# master_jorge3newIMU.net
KiCad netlist of a schematic drawn in EAGLE
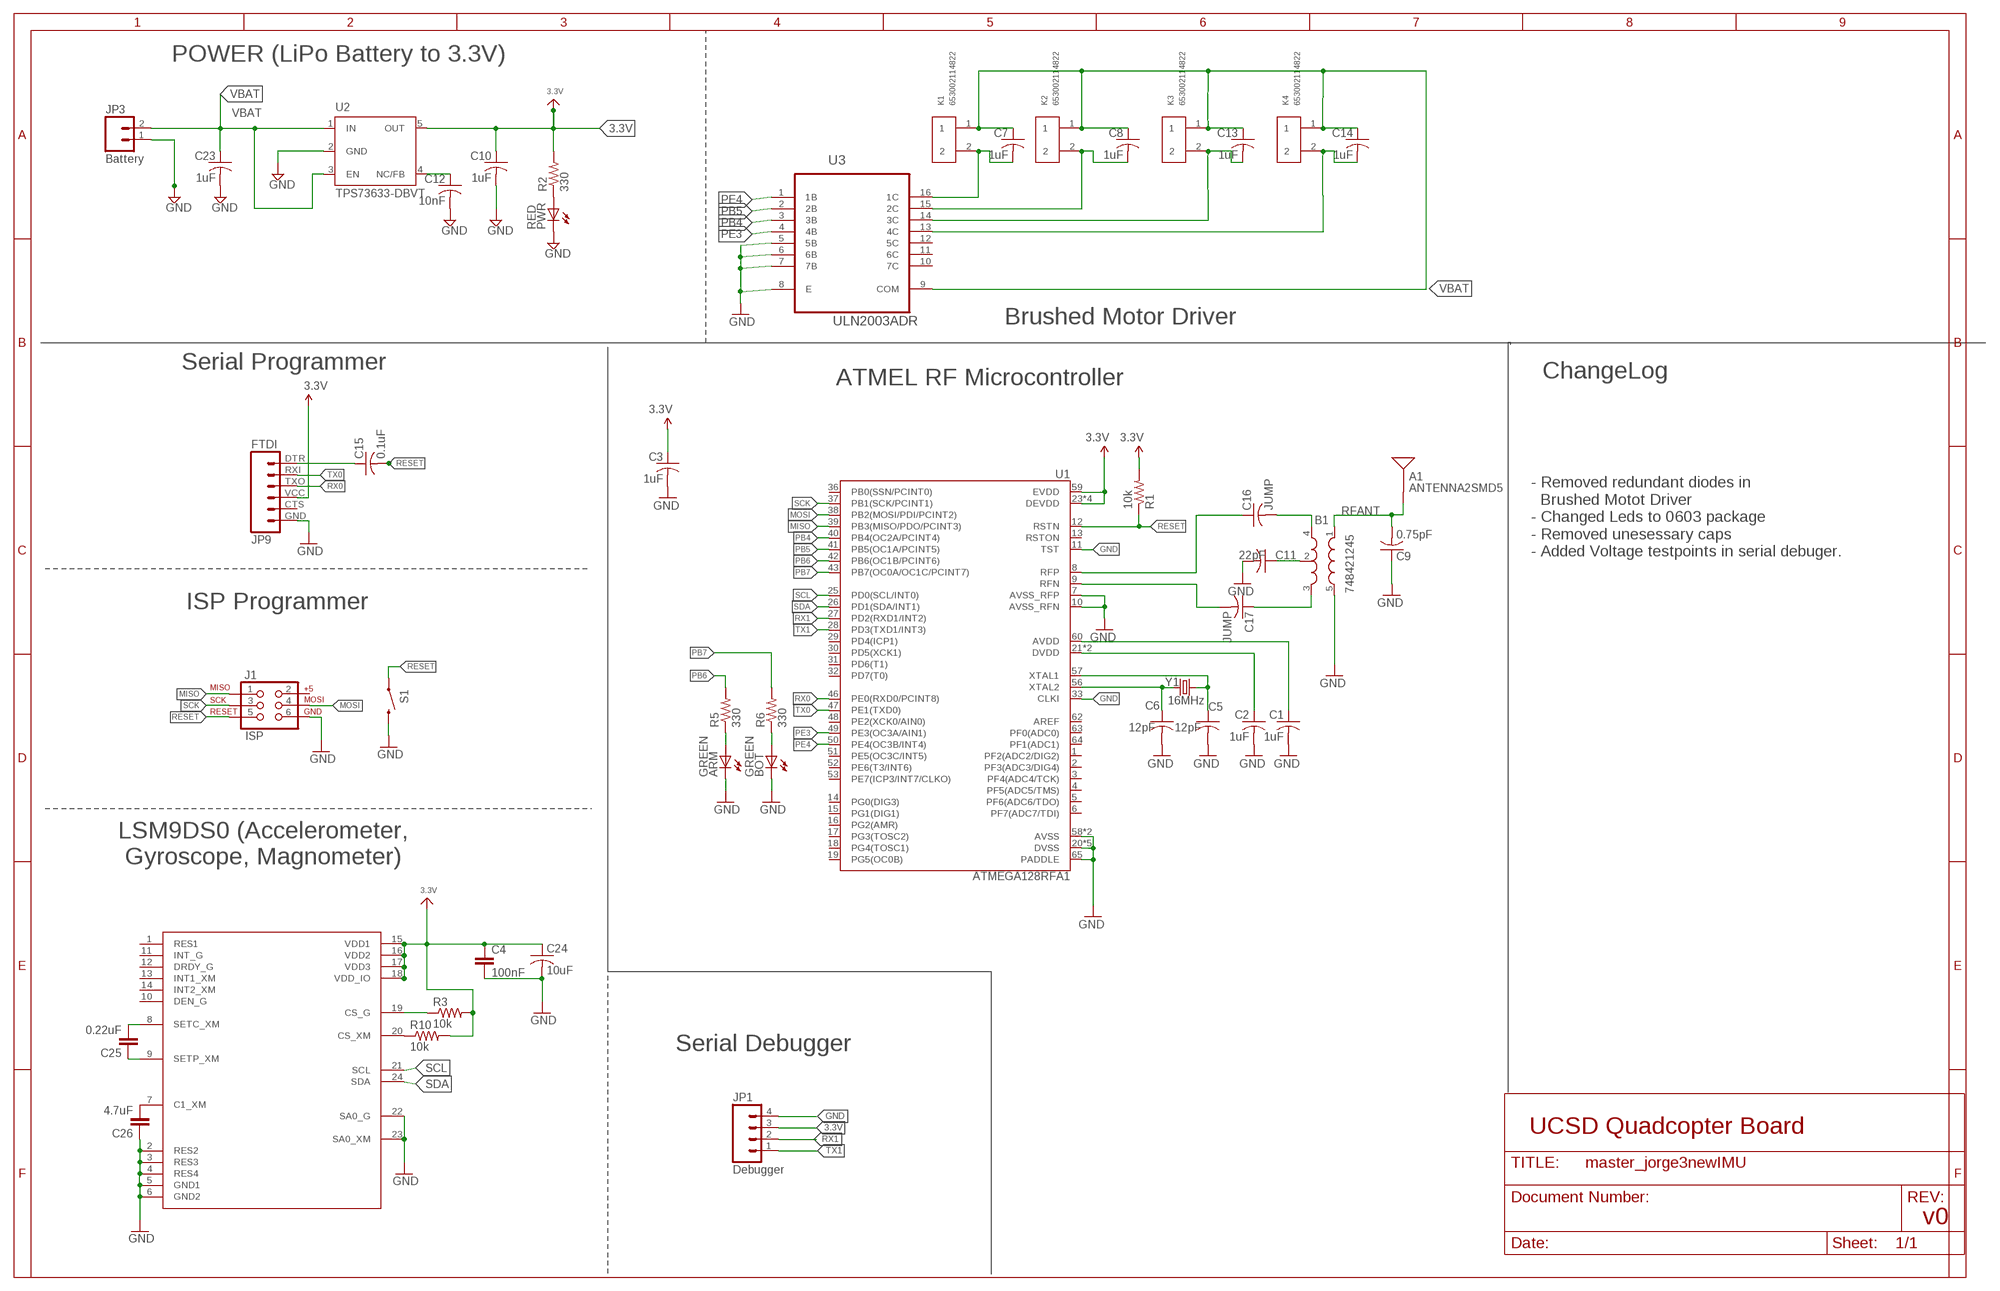
[diagram p0: schematic, sheet 1]

(export (version "E")
  (design (tool "Eeschema 10.0.6"))
  (components
    (comp (ref "A1")
      (value "ANTENNA2SMD5")
      (footprint "eagle-import:ANTENNA-CHIP5")
      (libsource (lib "eagle-import") (part "ANTENNA2SMD5"))
    )
    (comp (ref "ARM")
      (value "GREEN")
      (footprint "eagle-import:CHIP-LED0805")
      (libsource (lib "eagle-import") (part "LEDCHIP-LED0805"))
    )
    (comp (ref "B1")
      (value "748421245")
      (footprint "eagle-import:BALUN")
      (libsource (lib "eagle-import") (part "BALUN0805"))
    )
    (comp (ref "BOT")
      (value "GREEN")
      (footprint "eagle-import:CHIP-LED0805")
      (libsource (lib "eagle-import") (part "LEDCHIP-LED0805"))
    )
    (comp (ref "C1")
      (value "1uF")
      (footprint "eagle-import:C0805")
      (libsource (lib "eagle-import") (part "resistor_C-USC0805"))
    )
    (comp (ref "C2")
      (value "1uF")
      (footprint "eagle-import:C0805")
      (libsource (lib "eagle-import") (part "resistor_C-USC0805"))
    )
    (comp (ref "C3")
      (value "1uF")
      (footprint "eagle-import:C0805")
      (libsource (lib "eagle-import") (part "resistor_C-USC0805"))
    )
    (comp (ref "C4")
      (value "100nF")
      (footprint "eagle-import:0805")
      (libsource (lib "eagle-import") (part "CAP0805"))
    )
    (comp (ref "C5")
      (value "12pF")
      (footprint "eagle-import:C0805")
      (libsource (lib "eagle-import") (part "resistor_C-USC0805"))
    )
    (comp (ref "C6")
      (value "12pF")
      (footprint "eagle-import:C0805")
      (libsource (lib "eagle-import") (part "resistor_C-USC0805"))
    )
    (comp (ref "C7")
      (value "1uF")
      (footprint "eagle-import:C0805")
      (libsource (lib "eagle-import") (part "resistor_C-USC0805"))
    )
    (comp (ref "C8")
      (value "1uF")
      (footprint "eagle-import:C0805")
      (libsource (lib "eagle-import") (part "resistor_C-USC0805"))
    )
    (comp (ref "C9")
      (value "0.75pF")
      (footprint "eagle-import:C0805")
      (libsource (lib "eagle-import") (part "resistor_C-USC0805"))
    )
    (comp (ref "C10")
      (value "1uF")
      (footprint "eagle-import:C0805")
      (libsource (lib "eagle-import") (part "resistor_C-USC0805"))
    )
    (comp (ref "C11")
      (value "22pF")
      (footprint "eagle-import:C0805")
      (libsource (lib "eagle-import") (part "resistor_C-USC0805"))
    )
    (comp (ref "C12")
      (value "10nF")
      (footprint "eagle-import:C0805")
      (libsource (lib "eagle-import") (part "resistor_C-USC0805"))
    )
    (comp (ref "C13")
      (value "1uF")
      (footprint "eagle-import:C0805")
      (libsource (lib "eagle-import") (part "resistor_C-USC0805"))
    )
    (comp (ref "C14")
      (value "1uF")
      (footprint "eagle-import:C0805")
      (libsource (lib "eagle-import") (part "resistor_C-USC0805"))
    )
    (comp (ref "C15")
      (value "0.1uF")
      (footprint "eagle-import:C0805")
      (libsource (lib "eagle-import") (part "resistor_C-USC0805"))
    )
    (comp (ref "C16")
      (value "JUMP")
      (footprint "eagle-import:C0805")
      (libsource (lib "eagle-import") (part "resistor_C-USC0805"))
    )
    (comp (ref "C17")
      (value "JUMP")
      (footprint "eagle-import:C0805")
      (libsource (lib "eagle-import") (part "resistor_C-USC0805"))
    )
    (comp (ref "C23")
      (value "1uF")
      (footprint "eagle-import:C0805")
      (libsource (lib "eagle-import") (part "resistor_C-USC0805"))
    )
    (comp (ref "C24")
      (value "10uF")
      (footprint "eagle-import:C0805")
      (libsource (lib "eagle-import") (part "C-USC0805"))
    )
    (comp (ref "C25")
      (value "0.22uF")
      (footprint "eagle-import:0805")
      (libsource (lib "eagle-import") (part "CAP0805"))
    )
    (comp (ref "C26")
      (value "4.7uF")
      (footprint "eagle-import:0805")
      (libsource (lib "eagle-import") (part "CAP0805"))
    )
    (comp (ref "J1")
      (value "ISP")
      (footprint "eagle-import:2X3-NS")
      (libsource (lib "eagle-import") (part "AVR_SPI_PRG_6NS"))
    )
    (comp (ref "JP1")
      (value "Debugger")
      (footprint "eagle-import:1X04")
      (libsource (lib "eagle-import") (part "M04PTH"))
    )
    (comp (ref "JP3")
      (value "Battery")
      (footprint "eagle-import:1X02")
      (libsource (lib "eagle-import") (part "M02PTH"))
    )
    (comp (ref "JP9")
      (value "FTDI")
      (footprint "eagle-import:FTDI_BASIC")
      (libsource (lib "eagle-import") (part "FTDI_BASICPTH"))
    )
    (comp (ref "K1")
      (value "653002114822")
      (footprint "eagle-import:653002114822")
      (libsource (lib "eagle-import") (part "653002114822"))
    )
    (comp (ref "K2")
      (value "653002114822")
      (footprint "eagle-import:653002114822")
      (libsource (lib "eagle-import") (part "653002114822"))
    )
    (comp (ref "K3")
      (value "653002114822")
      (footprint "eagle-import:653002114822")
      (libsource (lib "eagle-import") (part "653002114822"))
    )
    (comp (ref "K4")
      (value "653002114822")
      (footprint "eagle-import:653002114822")
      (libsource (lib "eagle-import") (part "653002114822"))
    )
    (comp (ref "PWR")
      (value "RED")
      (footprint "eagle-import:CHIP-LED0805")
      (libsource (lib "eagle-import") (part "LEDCHIP-LED0805"))
    )
    (comp (ref "R1")
      (value "10k")
      (footprint "eagle-import:R0805")
      (libsource (lib "eagle-import") (part "R-US_R0805"))
    )
    (comp (ref "R2")
      (value "330")
      (footprint "eagle-import:R0805")
      (libsource (lib "eagle-import") (part "R-US_R0805"))
    )
    (comp (ref "R3")
      (value "10k")
      (footprint "eagle-import:0805")
      (libsource (lib "eagle-import") (part "RESISTOR0805-RES"))
    )
    (comp (ref "R5")
      (value "330")
      (footprint "eagle-import:R0805")
      (libsource (lib "eagle-import") (part "R-US_R0805"))
    )
    (comp (ref "R6")
      (value "330")
      (footprint "eagle-import:R0805")
      (libsource (lib "eagle-import") (part "R-US_R0805"))
    )
    (comp (ref "R10")
      (value "10k")
      (footprint "eagle-import:0805")
      (libsource (lib "eagle-import") (part "RESISTOR0805-RES"))
    )
    (comp (ref "S1")
      (value "SWITCH-MOMENTARY-2SMD")
      (footprint "eagle-import:TACTILE_SWITCH_SMD")
      (libsource (lib "eagle-import") (part "SWITCH-MOMENTARY-2SMD"))
    )
    (comp (ref "U1")
      (value "ATMEGA128RFA1")
      (footprint "eagle-import:QFN-64")
      (libsource (lib "eagle-import") (part "ATMEGA128RFA1"))
    )
    (comp (ref "U2")
      (value "TPS73633-DBVT")
      (footprint "eagle-import:SOT23-DBV")
      (libsource (lib "eagle-import") (part "TPS73633-DBVT"))
    )
    (comp (ref "U3")
      (value "ULN2003ADR")
      (footprint "eagle-import:SOIC127P600X175-16N")
      (libsource (lib "eagle-import") (part "ULN2003ADR"))
    )
    (comp (ref "U4")
      (value "LSM9DS0")
      (footprint "eagle-import:LGA-24")
      (libsource (lib "eagle-import") (part "LSM9DS0"))
    )
    (comp (ref "Y1")
      (value "16MHz")
      (footprint "eagle-import:CRYSTAL-SMD-5X3")
      (libsource (lib "eagle-import") (part "CRYSTAL5X3"))
    )
  )
  (nets
    (net (code "1") (name "/RFANT") (class "Default")
      (node (ref "A1") (pin "FEED") (pinfunction "SIGNAL_FEED") (pintype "bidirectional"))
      (node (ref "B1") (pin "1") (pinfunction "IN_1") (pintype "bidirectional"))
      (node (ref "C9") (pin "2") (pinfunction "2_2") (pintype "passive"))
    )
    (net (code "2") (name "3.3V") (class "Default")
      (node (ref "C10") (pin "1") (pinfunction "1_1") (pintype "passive"))
      (node (ref "C24") (pin "1") (pinfunction "1_1") (pintype "passive"))
      (node (ref "C3") (pin "1") (pinfunction "1_1") (pintype "passive"))
      (node (ref "C4") (pin "1") (pinfunction "1_1") (pintype "passive"))
      (node (ref "JP1") (pin "3") (pinfunction "3_3") (pintype "passive"))
      (node (ref "JP9") (pin "VCC") (pinfunction "4_VCC") (pintype "passive"))
      (node (ref "R1") (pin "2") (pinfunction "2_2") (pintype "passive"))
      (node (ref "R10") (pin "2") (pinfunction "2_2") (pintype "passive"))
      (node (ref "R2") (pin "2") (pinfunction "2_2") (pintype "passive"))
      (node (ref "R3") (pin "2") (pinfunction "2_2") (pintype "passive"))
      (node (ref "U1") (pin "23") (pinfunction "DEVDD_23") (pintype "bidirectional"))
      (node (ref "U1") (pin "34") (pinfunction "DEVDD_34") (pintype "bidirectional"))
      (node (ref "U1") (pin "44") (pinfunction "DEVDD_44") (pintype "bidirectional"))
      (node (ref "U1") (pin "54") (pinfunction "DEVDD_54") (pintype "bidirectional"))
      (node (ref "U1") (pin "59") (pinfunction "EVDD_59") (pintype "bidirectional"))
      (node (ref "U2") (pin "5") (pinfunction "OUT_5") (pintype "passive"))
      (node (ref "U4") (pin "15") (pinfunction "VDD1_15") (pintype "bidirectional"))
      (node (ref "U4") (pin "16") (pinfunction "VDD2_16") (pintype "bidirectional"))
      (node (ref "U4") (pin "17") (pinfunction "VDD3_17") (pintype "bidirectional"))
      (node (ref "U4") (pin "18") (pinfunction "VDD_IO_18") (pintype "bidirectional"))
    )
    (net (code "3") (name "GND") (class "Default")
      (node (ref "ARM") (pin "C") (pinfunction "C_C") (pintype "passive"))
      (node (ref "B1") (pin "5") (pinfunction "GND_5") (pintype "bidirectional"))
      (node (ref "BOT") (pin "C") (pinfunction "C_C") (pintype "passive"))
      (node (ref "C1") (pin "2") (pinfunction "2_2") (pintype "passive"))
      (node (ref "C10") (pin "2") (pinfunction "2_2") (pintype "passive"))
      (node (ref "C11") (pin "2") (pinfunction "2_2") (pintype "passive"))
      (node (ref "C12") (pin "2") (pinfunction "2_2") (pintype "passive"))
      (node (ref "C2") (pin "2") (pinfunction "2_2") (pintype "passive"))
      (node (ref "C23") (pin "2") (pinfunction "2_2") (pintype "passive"))
      (node (ref "C24") (pin "2") (pinfunction "2_2") (pintype "passive"))
      (node (ref "C26") (pin "1") (pinfunction "1_1") (pintype "passive"))
      (node (ref "C3") (pin "2") (pinfunction "2_2") (pintype "passive"))
      (node (ref "C4") (pin "2") (pinfunction "2_2") (pintype "passive"))
      (node (ref "C5") (pin "2") (pinfunction "2_2") (pintype "passive"))
      (node (ref "C6") (pin "2") (pinfunction "2_2") (pintype "passive"))
      (node (ref "C9") (pin "1") (pinfunction "1_1") (pintype "passive"))
      (node (ref "J1") (pin "6") (pinfunction "6_6") (pintype "passive"))
      (node (ref "JP1") (pin "4") (pinfunction "4_4") (pintype "passive"))
      (node (ref "JP3") (pin "1") (pinfunction "1_1") (pintype "passive"))
      (node (ref "JP9") (pin "GND") (pinfunction "6_GND") (pintype "passive"))
      (node (ref "PWR") (pin "C") (pinfunction "C_C") (pintype "passive"))
      (node (ref "S1") (pin "3") (pinfunction "2_3") (pintype "passive"))
      (node (ref "U1") (pin "10") (pinfunction "AVSS_RFN_10") (pintype "bidirectional"))
      (node (ref "U1") (pin "11") (pinfunction "TST_11") (pintype "bidirectional"))
      (node (ref "U1") (pin "20") (pinfunction "DVSS_20") (pintype "bidirectional"))
      (node (ref "U1") (pin "24") (pinfunction "DVSS_24") (pintype "bidirectional"))
      (node (ref "U1") (pin "33") (pinfunction "CLKI_33") (pintype "bidirectional"))
      (node (ref "U1") (pin "35") (pinfunction "DVSS_35") (pintype "bidirectional"))
      (node (ref "U1") (pin "45") (pinfunction "DVSS_45") (pintype "bidirectional"))
      (node (ref "U1") (pin "55") (pinfunction "DVSS_55") (pintype "bidirectional"))
      (node (ref "U1") (pin "58") (pinfunction "AVSS_58") (pintype "bidirectional"))
      (node (ref "U1") (pin "61") (pinfunction "AVSS_61") (pintype "bidirectional"))
      (node (ref "U1") (pin "65") (pinfunction "PADDLE_65") (pintype "bidirectional"))
      (node (ref "U1") (pin "7") (pinfunction "AVSS_RFP_7") (pintype "bidirectional"))
      (node (ref "U2") (pin "2") (pinfunction "GND_2") (pintype "input"))
      (node (ref "U3") (pin "5") (pinfunction "5B_5") (pintype "input"))
      (node (ref "U3") (pin "6") (pinfunction "6B_6") (pintype "input"))
      (node (ref "U3") (pin "7") (pinfunction "7B_7") (pintype "input"))
      (node (ref "U3") (pin "8") (pinfunction "E_8") (pintype "input"))
      (node (ref "U4") (pin "2") (pinfunction "RES2_2") (pintype "bidirectional"))
      (node (ref "U4") (pin "22") (pinfunction "SA0_G_22") (pintype "bidirectional"))
      (node (ref "U4") (pin "23") (pinfunction "SA0_XM_23") (pintype "bidirectional"))
      (node (ref "U4") (pin "3") (pinfunction "RES3_3") (pintype "bidirectional"))
      (node (ref "U4") (pin "4") (pinfunction "RES4_4") (pintype "bidirectional"))
      (node (ref "U4") (pin "5") (pinfunction "GND1_5") (pintype "bidirectional"))
      (node (ref "U4") (pin "6") (pinfunction "GND2_6") (pintype "bidirectional"))
    )
    (net (code "4") (name "MISO") (class "Default")
      (node (ref "J1") (pin "1") (pinfunction "1_1") (pintype "passive"))
      (node (ref "U1") (pin "39") (pinfunction "PB3(MISO/PDO/PCINT3)_39") (pintype "bidirectional"))
    )
    (net (code "5") (name "MOSI") (class "Default")
      (node (ref "J1") (pin "4") (pinfunction "4_4") (pintype "passive"))
      (node (ref "U1") (pin "38") (pinfunction "PB2(MOSI/PDI/PCINT2)_38") (pintype "bidirectional"))
    )
    (net (code "6") (name "Net-(ARM-PadA)") (class "Default")
      (node (ref "ARM") (pin "A") (pinfunction "A_A") (pintype "passive"))
      (node (ref "R5") (pin "1") (pinfunction "1_1") (pintype "passive"))
    )
    (net (code "7") (name "Net-(B1-GND-Pad2)") (class "Default")
      (node (ref "B1") (pin "2") (pinfunction "GND_2") (pintype "bidirectional"))
      (node (ref "C11") (pin "1") (pinfunction "1_1") (pintype "passive"))
    )
    (net (code "8") (name "Net-(B1-OUT1)") (class "Default")
      (node (ref "B1") (pin "4") (pinfunction "OUT1_4") (pintype "bidirectional"))
      (node (ref "C16") (pin "2") (pinfunction "2_2") (pintype "passive"))
    )
    (net (code "9") (name "Net-(B1-OUT2)") (class "Default")
      (node (ref "B1") (pin "3") (pinfunction "OUT2_3") (pintype "bidirectional"))
      (node (ref "C17") (pin "1") (pinfunction "1_1") (pintype "passive"))
    )
    (net (code "10") (name "Net-(BOT-PadA)") (class "Default")
      (node (ref "BOT") (pin "A") (pinfunction "A_A") (pintype "passive"))
      (node (ref "R6") (pin "1") (pinfunction "1_1") (pintype "passive"))
    )
    (net (code "11") (name "Net-(C2-Pad1)") (class "Default")
      (node (ref "C2") (pin "1") (pinfunction "1_1") (pintype "passive"))
      (node (ref "U1") (pin "21") (pinfunction "DVDD_21") (pintype "bidirectional"))
      (node (ref "U1") (pin "22") (pinfunction "DVDD_22") (pintype "bidirectional"))
    )
    (net (code "12") (name "Net-(JP9-1)") (class "Default")
      (node (ref "C15") (pin "1") (pinfunction "1_1") (pintype "passive"))
      (node (ref "JP9") (pin "DTR") (pinfunction "1_DTR") (pintype "passive"))
    )
    (net (code "13") (name "Net-(PWR-PadA)") (class "Default")
      (node (ref "PWR") (pin "A") (pinfunction "A_A") (pintype "passive"))
      (node (ref "R2") (pin "1") (pinfunction "1_1") (pintype "passive"))
    )
    (net (code "14") (name "Net-(U1-AVDD)") (class "Default")
      (node (ref "C1") (pin "1") (pinfunction "1_1") (pintype "passive"))
      (node (ref "U1") (pin "60") (pinfunction "AVDD_60") (pintype "bidirectional"))
    )
    (net (code "15") (name "Net-(U1-RFN)") (class "Default")
      (node (ref "C17") (pin "2") (pinfunction "2_2") (pintype "passive"))
      (node (ref "U1") (pin "9") (pinfunction "RFN_9") (pintype "bidirectional"))
    )
    (net (code "16") (name "Net-(U1-RFP)") (class "Default")
      (node (ref "C16") (pin "1") (pinfunction "1_1") (pintype "passive"))
      (node (ref "U1") (pin "8") (pinfunction "RFP_8") (pintype "bidirectional"))
    )
    (net (code "17") (name "Net-(U1-XTAL1)") (class "Default")
      (node (ref "C5") (pin "1") (pinfunction "1_1") (pintype "passive"))
      (node (ref "U1") (pin "57") (pinfunction "XTAL1_57") (pintype "bidirectional"))
      (node (ref "Y1") (pin "3") (pinfunction "2_3") (pintype "passive"))
    )
    (net (code "18") (name "Net-(U1-XTAL2)") (class "Default")
      (node (ref "C6") (pin "1") (pinfunction "1_1") (pintype "passive"))
      (node (ref "U1") (pin "56") (pinfunction "XTAL2_56") (pintype "bidirectional"))
      (node (ref "Y1") (pin "1") (pinfunction "1_1") (pintype "passive"))
    )
    (net (code "19") (name "Net-(U2-NC{slash}FB)") (class "Default")
      (node (ref "C12") (pin "1") (pinfunction "1_1") (pintype "passive"))
      (node (ref "U2") (pin "4") (pinfunction "NC/FB_4") (pintype "passive"))
    )
    (net (code "20") (name "Net-(U3-1C)") (class "Default")
      (node (ref "C7") (pin "2") (pinfunction "2_2") (pintype "passive"))
      (node (ref "K1") (pin "2") (pinfunction "2_2") (pintype "bidirectional"))
      (node (ref "U3") (pin "16") (pinfunction "1C_16") (pintype "output"))
    )
    (net (code "21") (name "Net-(U3-2C)") (class "Default")
      (node (ref "C8") (pin "2") (pinfunction "2_2") (pintype "passive"))
      (node (ref "K2") (pin "2") (pinfunction "2_2") (pintype "bidirectional"))
      (node (ref "U3") (pin "15") (pinfunction "2C_15") (pintype "output"))
    )
    (net (code "22") (name "Net-(U3-3C)") (class "Default")
      (node (ref "C13") (pin "2") (pinfunction "2_2") (pintype "passive"))
      (node (ref "K3") (pin "2") (pinfunction "2_2") (pintype "bidirectional"))
      (node (ref "U3") (pin "14") (pinfunction "3C_14") (pintype "output"))
    )
    (net (code "23") (name "Net-(U3-4C)") (class "Default")
      (node (ref "C14") (pin "2") (pinfunction "2_2") (pintype "passive"))
      (node (ref "K4") (pin "2") (pinfunction "2_2") (pintype "bidirectional"))
      (node (ref "U3") (pin "13") (pinfunction "4C_13") (pintype "output"))
    )
    (net (code "24") (name "Net-(U4-C1_XM)") (class "Default")
      (node (ref "C26") (pin "2") (pinfunction "2_2") (pintype "passive"))
      (node (ref "U4") (pin "7") (pinfunction "C1_XM_7") (pintype "bidirectional"))
    )
    (net (code "25") (name "Net-(U4-CS_G)") (class "Default")
      (node (ref "R3") (pin "1") (pinfunction "1_1") (pintype "passive"))
      (node (ref "U4") (pin "19") (pinfunction "CS_G_19") (pintype "bidirectional"))
    )
    (net (code "26") (name "Net-(U4-CS_XM)") (class "Default")
      (node (ref "R10") (pin "1") (pinfunction "1_1") (pintype "passive"))
      (node (ref "U4") (pin "20") (pinfunction "CS_XM_20") (pintype "bidirectional"))
    )
    (net (code "27") (name "Net-(U4-SETC_XM)") (class "Default")
      (node (ref "C25") (pin "2") (pinfunction "2_2") (pintype "passive"))
      (node (ref "U4") (pin "8") (pinfunction "SETC_XM_8") (pintype "bidirectional"))
    )
    (net (code "28") (name "Net-(U4-SETP_XM)") (class "Default")
      (node (ref "C25") (pin "1") (pinfunction "1_1") (pintype "passive"))
      (node (ref "U4") (pin "9") (pinfunction "SETP_XM_9") (pintype "bidirectional"))
    )
    (net (code "29") (name "PB4") (class "Default")
      (node (ref "U1") (pin "40") (pinfunction "PB4(OC2A/PCINT4)_40") (pintype "bidirectional"))
      (node (ref "U3") (pin "3") (pinfunction "3B_3") (pintype "input"))
    )
    (net (code "30") (name "PB5") (class "Default")
      (node (ref "U1") (pin "41") (pinfunction "PB5(OC1A/PCINT5)_41") (pintype "bidirectional"))
      (node (ref "U3") (pin "2") (pinfunction "2B_2") (pintype "input"))
    )
    (net (code "31") (name "PB6") (class "Default")
      (node (ref "R5") (pin "2") (pinfunction "2_2") (pintype "passive"))
      (node (ref "U1") (pin "42") (pinfunction "PB6(OC1B/PCINT6)_42") (pintype "bidirectional"))
    )
    (net (code "32") (name "PB7") (class "Default")
      (node (ref "R6") (pin "2") (pinfunction "2_2") (pintype "passive"))
      (node (ref "U1") (pin "43") (pinfunction "PB7(OC0A/OC1C/PCINT7)_43") (pintype "bidirectional"))
    )
    (net (code "33") (name "PE3") (class "Default")
      (node (ref "U1") (pin "49") (pinfunction "PE3(OC3A/AIN1)_49") (pintype "bidirectional"))
      (node (ref "U3") (pin "4") (pinfunction "4B_4") (pintype "input"))
    )
    (net (code "34") (name "PE4") (class "Default")
      (node (ref "U1") (pin "50") (pinfunction "PE4(OC3B/INT4)_50") (pintype "bidirectional"))
      (node (ref "U3") (pin "1") (pinfunction "1B_1") (pintype "input"))
    )
    (net (code "35") (name "RESET") (class "Default")
      (node (ref "C15") (pin "2") (pinfunction "2_2") (pintype "passive"))
      (node (ref "J1") (pin "5") (pinfunction "5_5") (pintype "passive"))
      (node (ref "R1") (pin "1") (pinfunction "1_1") (pintype "passive"))
      (node (ref "S1") (pin "1") (pinfunction "1_1") (pintype "passive"))
      (node (ref "U1") (pin "12") (pinfunction "RSTN_12") (pintype "bidirectional"))
    )
    (net (code "36") (name "RX0") (class "Default")
      (node (ref "JP9") (pin "TXO") (pinfunction "3_TXO") (pintype "passive"))
      (node (ref "U1") (pin "46") (pinfunction "PE0(RXD0/PCINT8)_46") (pintype "bidirectional"))
    )
    (net (code "37") (name "RX1") (class "Default")
      (node (ref "JP1") (pin "2") (pinfunction "2_2") (pintype "passive"))
      (node (ref "U1") (pin "27") (pinfunction "PD2(RXD1/INT2)_27") (pintype "bidirectional"))
    )
    (net (code "38") (name "SCK") (class "Default")
      (node (ref "J1") (pin "3") (pinfunction "3_3") (pintype "passive"))
      (node (ref "U1") (pin "37") (pinfunction "PB1(SCK/PCINT1)_37") (pintype "bidirectional"))
    )
    (net (code "39") (name "SCL") (class "Default")
      (node (ref "U1") (pin "25") (pinfunction "PD0(SCL/INT0)_25") (pintype "bidirectional"))
      (node (ref "U4") (pin "21") (pinfunction "SCL_21") (pintype "bidirectional"))
    )
    (net (code "40") (name "SDA") (class "Default")
      (node (ref "U1") (pin "26") (pinfunction "PD1(SDA/INT1)_26") (pintype "bidirectional"))
      (node (ref "U4") (pin "24") (pinfunction "SDA_24") (pintype "bidirectional"))
    )
    (net (code "41") (name "TX0") (class "Default")
      (node (ref "JP9") (pin "RXI") (pinfunction "2_RXI") (pintype "passive"))
      (node (ref "U1") (pin "47") (pinfunction "PE1(TXD0)_47") (pintype "bidirectional"))
    )
    (net (code "42") (name "TX1") (class "Default")
      (node (ref "JP1") (pin "1") (pinfunction "1_1") (pintype "passive"))
      (node (ref "U1") (pin "28") (pinfunction "PD3(TXD1/INT3)_28") (pintype "bidirectional"))
    )
    (net (code "43") (name "VBAT") (class "Default")
      (node (ref "C13") (pin "1") (pinfunction "1_1") (pintype "passive"))
      (node (ref "C14") (pin "1") (pinfunction "1_1") (pintype "passive"))
      (node (ref "C23") (pin "1") (pinfunction "1_1") (pintype "passive"))
      (node (ref "C7") (pin "1") (pinfunction "1_1") (pintype "passive"))
      (node (ref "C8") (pin "1") (pinfunction "1_1") (pintype "passive"))
      (node (ref "JP3") (pin "2") (pinfunction "2_2") (pintype "passive"))
      (node (ref "K1") (pin "1") (pinfunction "1_1") (pintype "bidirectional"))
      (node (ref "K2") (pin "1") (pinfunction "1_1") (pintype "bidirectional"))
      (node (ref "K3") (pin "1") (pinfunction "1_1") (pintype "bidirectional"))
      (node (ref "K4") (pin "1") (pinfunction "1_1") (pintype "bidirectional"))
      (node (ref "U2") (pin "1") (pinfunction "IN_1") (pintype "input"))
      (node (ref "U2") (pin "3") (pinfunction "EN_3") (pintype "power_in"))
      (node (ref "U3") (pin "9") (pinfunction "COM_9") (pintype "output"))
    )
    (net (code "44") (name "unconnected-(J1-Pad2)") (class "Default")
      (node (ref "J1") (pin "2") (pinfunction "2_2") (pintype "passive"))
    )
    (net (code "45") (name "unconnected-(JP9-5-PadCTS)") (class "Default")
      (node (ref "JP9") (pin "CTS") (pinfunction "5_CTS") (pintype "passive"))
    )
    (net (code "46") (name "unconnected-(U1-AREF-Pad62)") (class "Default")
      (node (ref "U1") (pin "62") (pinfunction "AREF_62") (pintype "bidirectional"))
    )
    (net (code "47") (name "unconnected-(U1-PB0(SSN{slash}PCINT0)-Pad36)") (class "Default")
      (node (ref "U1") (pin "36") (pinfunction "PB0(SSN/PCINT0)_36") (pintype "bidirectional"))
    )
    (net (code "48") (name "unconnected-(U1-PD4(ICP1)-Pad29)") (class "Default")
      (node (ref "U1") (pin "29") (pinfunction "PD4(ICP1)_29") (pintype "bidirectional"))
    )
    (net (code "49") (name "unconnected-(U1-PD5(XCK1)-Pad30)") (class "Default")
      (node (ref "U1") (pin "30") (pinfunction "PD5(XCK1)_30") (pintype "bidirectional"))
    )
    (net (code "50") (name "unconnected-(U1-PD6(T1)-Pad31)") (class "Default")
      (node (ref "U1") (pin "31") (pinfunction "PD6(T1)_31") (pintype "bidirectional"))
    )
    (net (code "51") (name "unconnected-(U1-PD7(T0)-Pad32)") (class "Default")
      (node (ref "U1") (pin "32") (pinfunction "PD7(T0)_32") (pintype "bidirectional"))
    )
    (net (code "52") (name "unconnected-(U1-PE2(XCK0{slash}AIN0)-Pad48)") (class "Default")
      (node (ref "U1") (pin "48") (pinfunction "PE2(XCK0/AIN0)_48") (pintype "bidirectional"))
    )
    (net (code "53") (name "unconnected-(U1-PE5(OC3C{slash}INT5)-Pad51)") (class "Default")
      (node (ref "U1") (pin "51") (pinfunction "PE5(OC3C/INT5)_51") (pintype "bidirectional"))
    )
    (net (code "54") (name "unconnected-(U1-PE6(T3{slash}INT6)-Pad52)") (class "Default")
      (node (ref "U1") (pin "52") (pinfunction "PE6(T3/INT6)_52") (pintype "bidirectional"))
    )
    (net (code "55") (name "unconnected-(U1-PE7(ICP3{slash}INT7{slash}CLKO)-Pad53)") (class "Default")
      (node (ref "U1") (pin "53") (pinfunction "PE7(ICP3/INT7/CLKO)_53") (pintype "bidirectional"))
    )
    (net (code "56") (name "unconnected-(U1-PF0(ADC0)-Pad63)") (class "Default")
      (node (ref "U1") (pin "63") (pinfunction "PF0(ADC0)_63") (pintype "bidirectional"))
    )
    (net (code "57") (name "unconnected-(U1-PF1(ADC1)-Pad64)") (class "Default")
      (node (ref "U1") (pin "64") (pinfunction "PF1(ADC1)_64") (pintype "bidirectional"))
    )
    (net (code "58") (name "unconnected-(U1-PF2(ADC2{slash}DIG2)-Pad1)") (class "Default")
      (node (ref "U1") (pin "1") (pinfunction "PF2(ADC2/DIG2)_1") (pintype "bidirectional"))
    )
    (net (code "59") (name "unconnected-(U1-PF3(ADC3{slash}DIG4)-Pad2)") (class "Default")
      (node (ref "U1") (pin "2") (pinfunction "PF3(ADC3/DIG4)_2") (pintype "bidirectional"))
    )
    (net (code "60") (name "unconnected-(U1-PF4(ADC4{slash}TCK)-Pad3)") (class "Default")
      (node (ref "U1") (pin "3") (pinfunction "PF4(ADC4/TCK)_3") (pintype "bidirectional"))
    )
    (net (code "61") (name "unconnected-(U1-PF5(ADC5{slash}TMS)-Pad4)") (class "Default")
      (node (ref "U1") (pin "4") (pinfunction "PF5(ADC5/TMS)_4") (pintype "bidirectional"))
    )
    (net (code "62") (name "unconnected-(U1-PF6(ADC6{slash}TDO)-Pad5)") (class "Default")
      (node (ref "U1") (pin "5") (pinfunction "PF6(ADC6/TDO)_5") (pintype "bidirectional"))
    )
    (net (code "63") (name "unconnected-(U1-PF7(ADC7{slash}TDI)-Pad6)") (class "Default")
      (node (ref "U1") (pin "6") (pinfunction "PF7(ADC7/TDI)_6") (pintype "bidirectional"))
    )
    (net (code "64") (name "unconnected-(U1-PG0(DIG3)-Pad14)") (class "Default")
      (node (ref "U1") (pin "14") (pinfunction "PG0(DIG3)_14") (pintype "bidirectional"))
    )
    (net (code "65") (name "unconnected-(U1-PG1(DIG1)-Pad15)") (class "Default")
      (node (ref "U1") (pin "15") (pinfunction "PG1(DIG1)_15") (pintype "bidirectional"))
    )
    (net (code "66") (name "unconnected-(U1-PG2(AMR)-Pad16)") (class "Default")
      (node (ref "U1") (pin "16") (pinfunction "PG2(AMR)_16") (pintype "bidirectional"))
    )
    (net (code "67") (name "unconnected-(U1-PG3(TOSC2)-Pad17)") (class "Default")
      (node (ref "U1") (pin "17") (pinfunction "PG3(TOSC2)_17") (pintype "bidirectional"))
    )
    (net (code "68") (name "unconnected-(U1-PG4(TOSC1)-Pad18)") (class "Default")
      (node (ref "U1") (pin "18") (pinfunction "PG4(TOSC1)_18") (pintype "bidirectional"))
    )
    (net (code "69") (name "unconnected-(U1-PG5(OC0B)-Pad19)") (class "Default")
      (node (ref "U1") (pin "19") (pinfunction "PG5(OC0B)_19") (pintype "bidirectional"))
    )
    (net (code "70") (name "unconnected-(U1-RSTON-Pad13)") (class "Default")
      (node (ref "U1") (pin "13") (pinfunction "RSTON_13") (pintype "bidirectional"))
    )
    (net (code "71") (name "unconnected-(U3-5C-Pad12)") (class "Default")
      (node (ref "U3") (pin "12") (pinfunction "5C_12") (pintype "output"))
    )
    (net (code "72") (name "unconnected-(U3-6C-Pad11)") (class "Default")
      (node (ref "U3") (pin "11") (pinfunction "6C_11") (pintype "output"))
    )
    (net (code "73") (name "unconnected-(U3-7C-Pad10)") (class "Default")
      (node (ref "U3") (pin "10") (pinfunction "7C_10") (pintype "output"))
    )
    (net (code "74") (name "unconnected-(U4-DEN_G-Pad10)") (class "Default")
      (node (ref "U4") (pin "10") (pinfunction "DEN_G_10") (pintype "bidirectional"))
    )
    (net (code "75") (name "unconnected-(U4-DRDY_G-Pad12)") (class "Default")
      (node (ref "U4") (pin "12") (pinfunction "DRDY_G_12") (pintype "bidirectional"))
    )
    (net (code "76") (name "unconnected-(U4-INT1_XM-Pad13)") (class "Default")
      (node (ref "U4") (pin "13") (pinfunction "INT1_XM_13") (pintype "bidirectional"))
    )
    (net (code "77") (name "unconnected-(U4-INT2_XM-Pad14)") (class "Default")
      (node (ref "U4") (pin "14") (pinfunction "INT2_XM_14") (pintype "bidirectional"))
    )
    (net (code "78") (name "unconnected-(U4-INT_G-Pad11)") (class "Default")
      (node (ref "U4") (pin "11") (pinfunction "INT_G_11") (pintype "bidirectional"))
    )
    (net (code "79") (name "unconnected-(U4-RES1-Pad1)") (class "Default")
      (node (ref "U4") (pin "1") (pinfunction "RES1_1") (pintype "bidirectional"))
    )
  )
)
